# amp.net
KiCad netlist of a schematic drawn in EAGLE
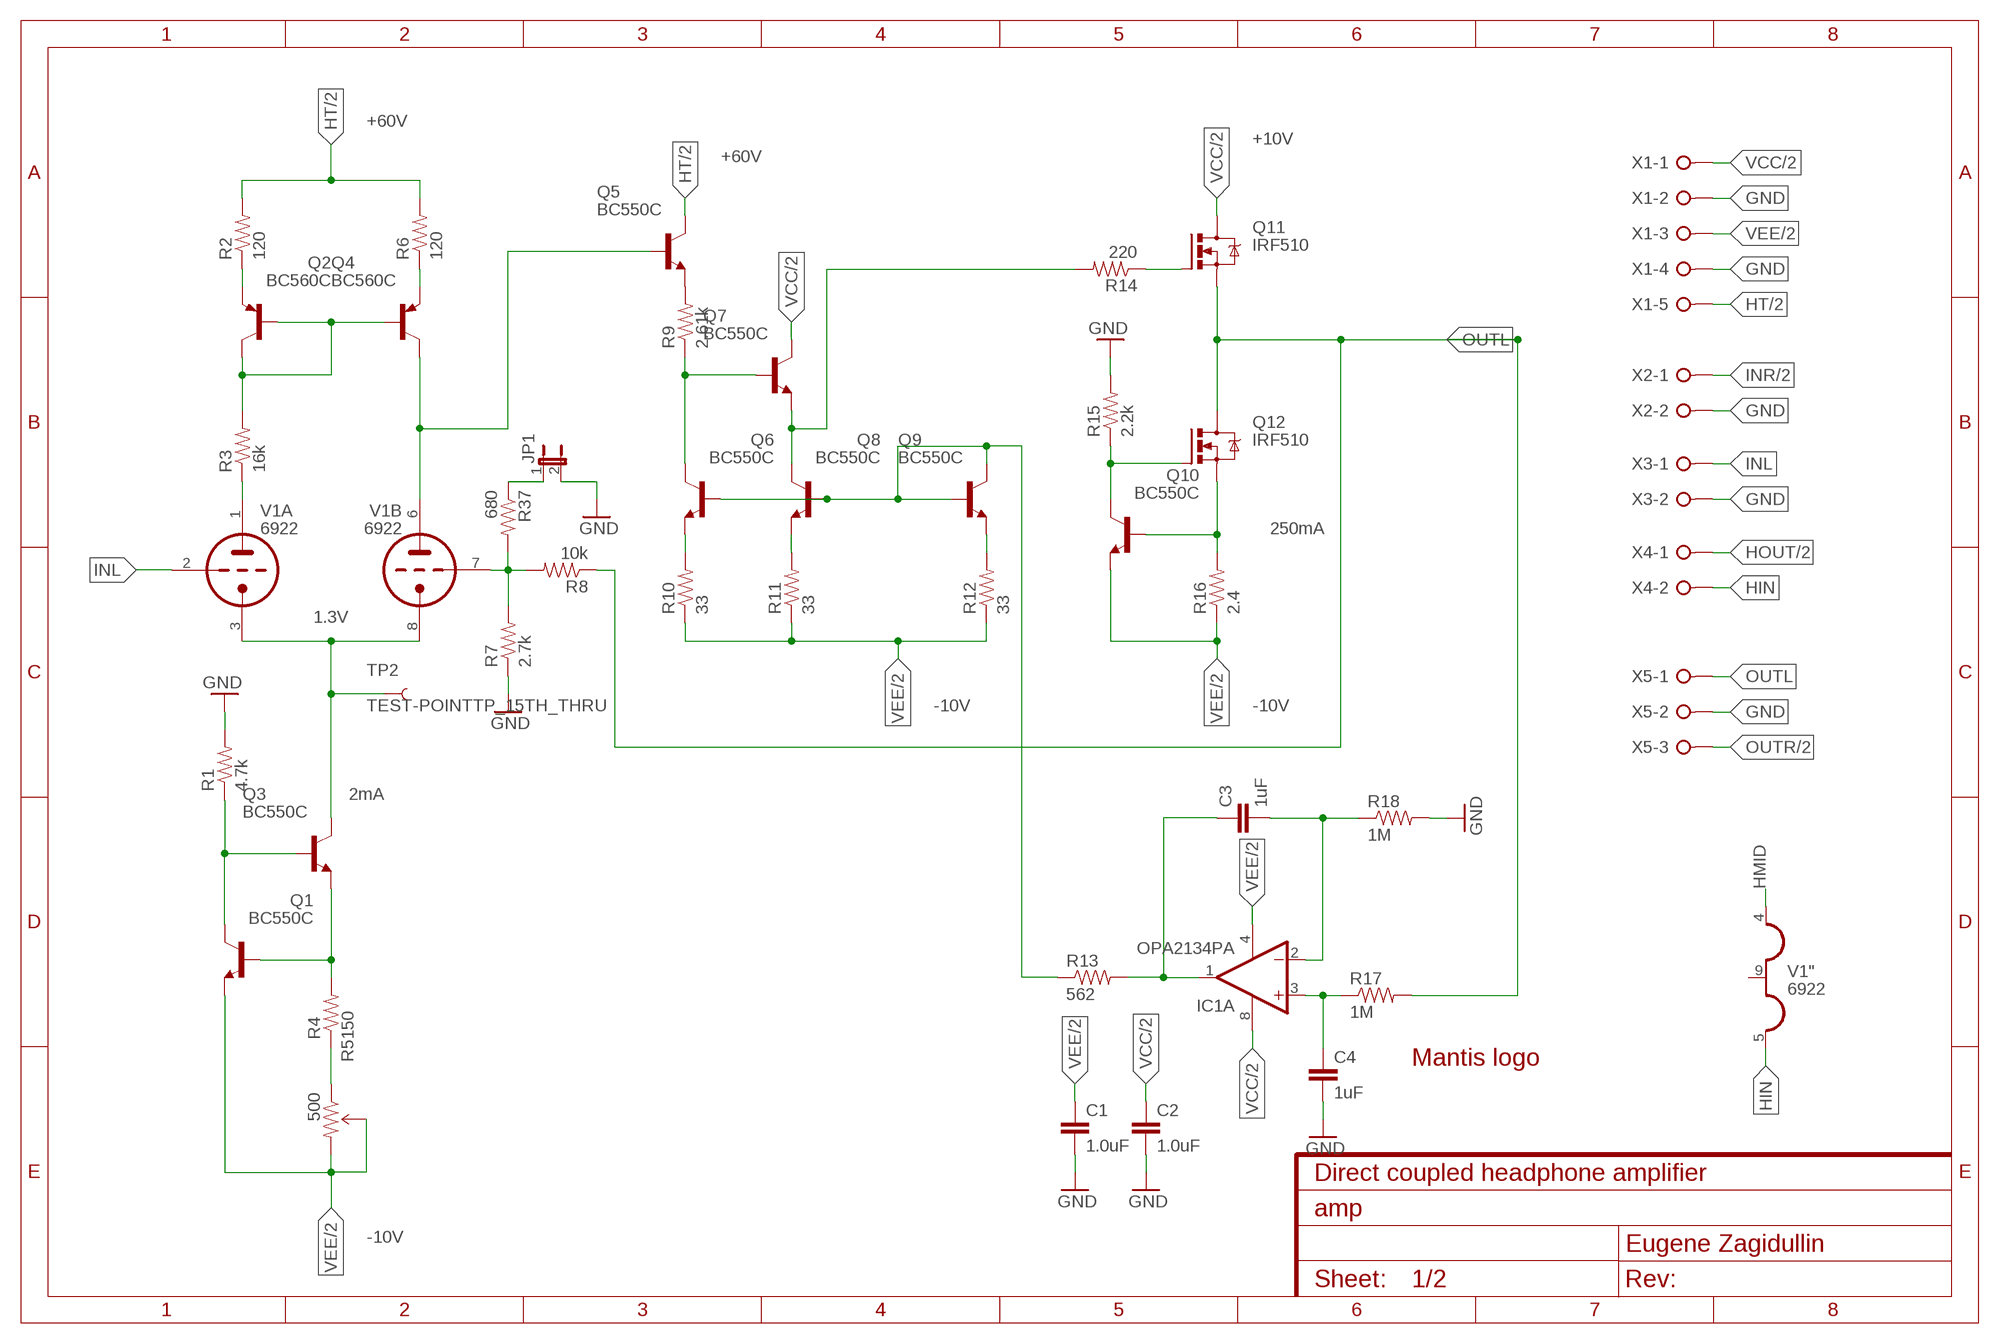
[diagram p0: schematic, sheet 1]
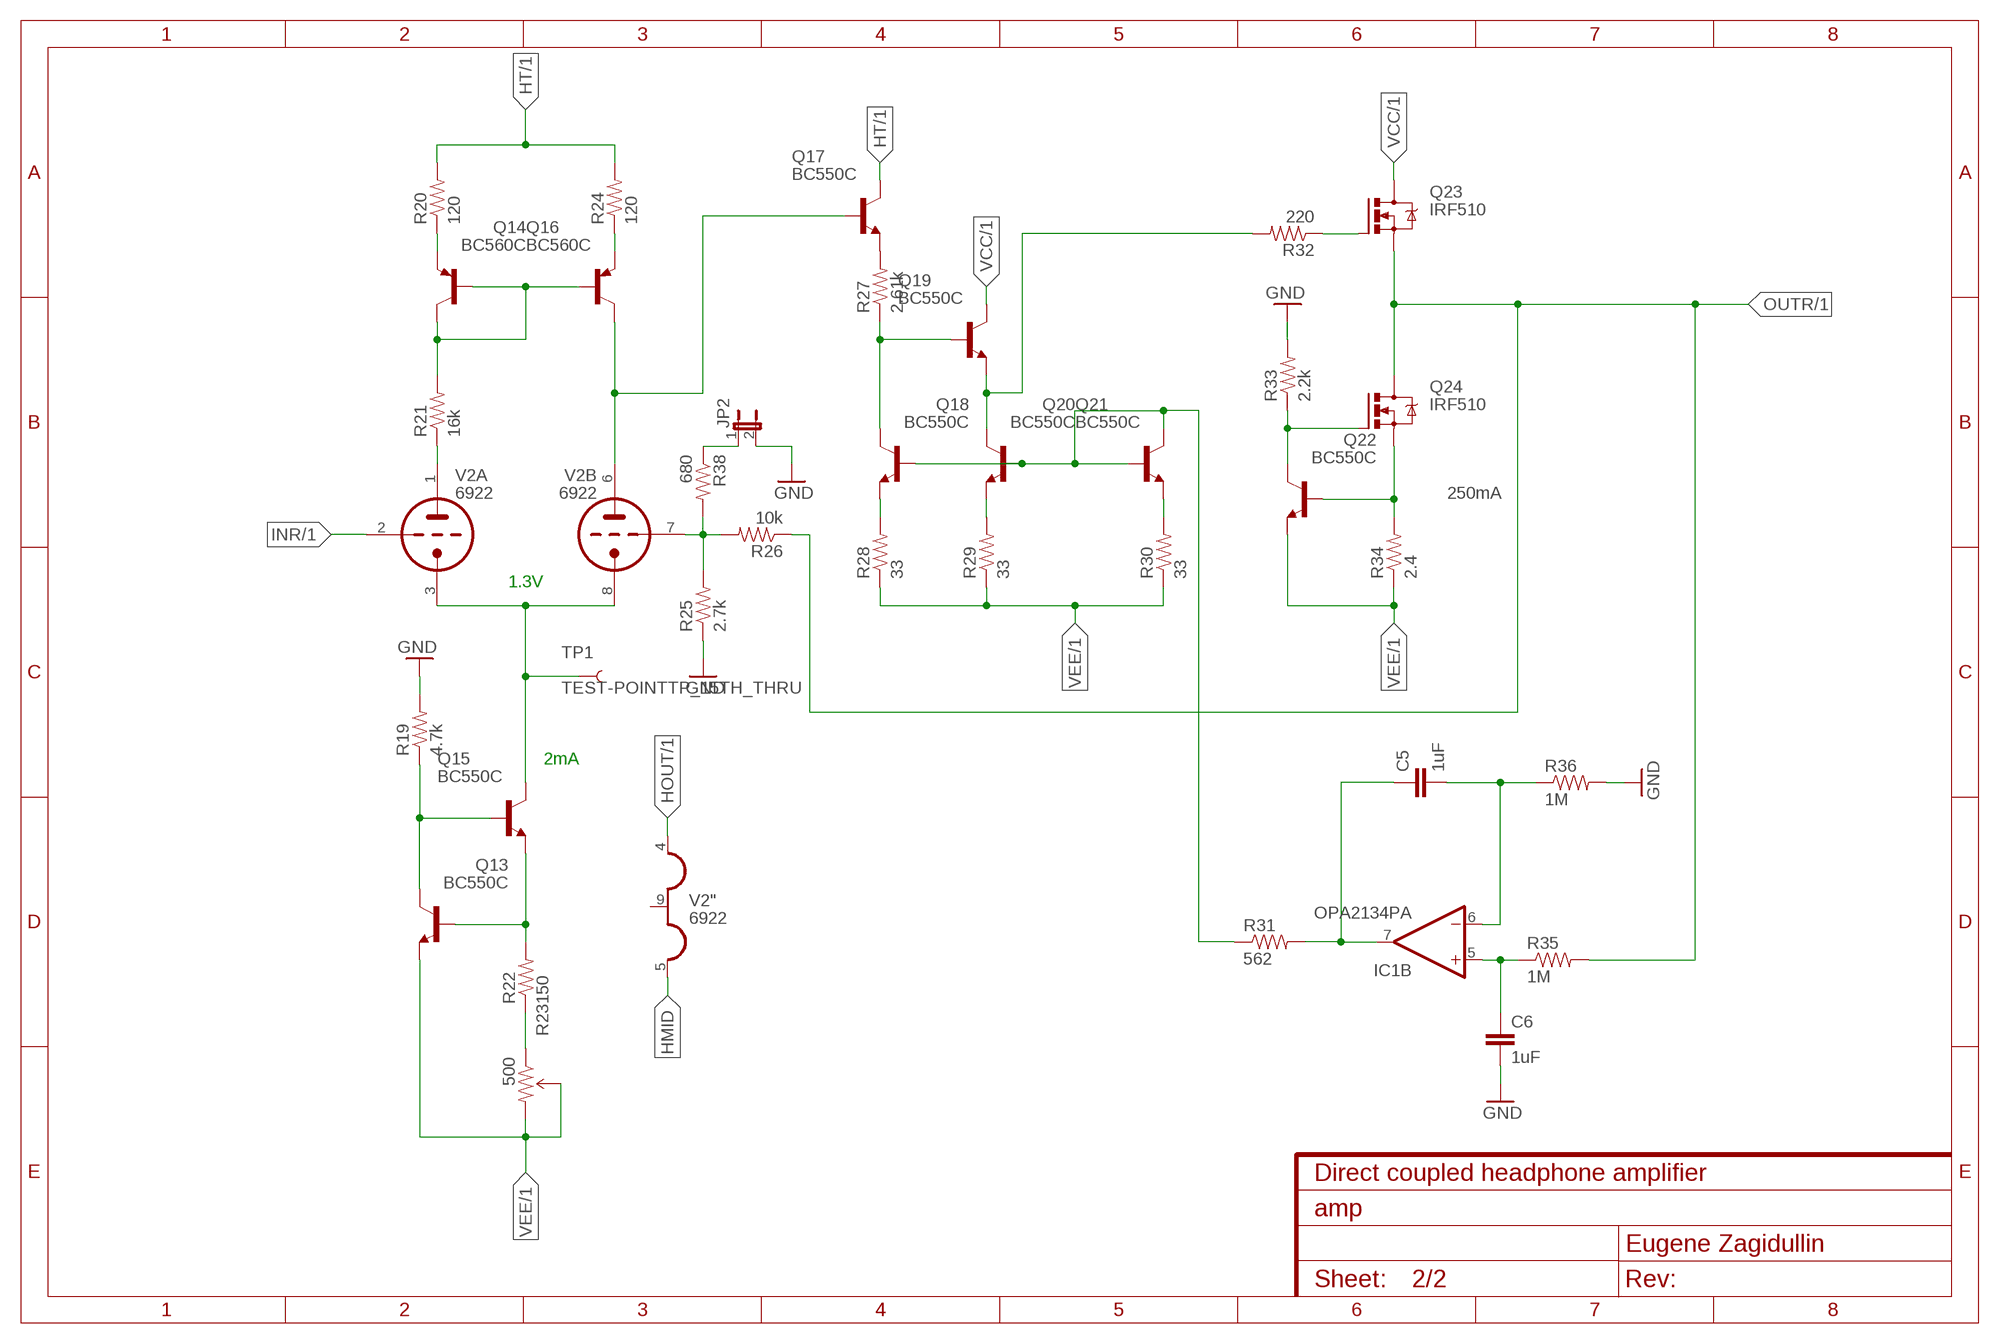
[diagram p1: schematic, sheet 2]

(export (version "E")
  (design (tool "Eeschema 10.0.6"))
  (components
    (comp (ref "C5")
      (value "1uF")
      (footprint "eagle-import:C5B5")
      (libsource (lib "eagle-import") (part "C5/5"))
    )
    (comp (ref "C6")
      (value "1uF")
      (footprint "eagle-import:C5B5")
      (libsource (lib "eagle-import") (part "C5/5"))
    )
    (comp (ref "IC1")
      (value "OPA2134PA")
      (footprint "eagle-import:DIL08")
      (libsource (lib "eagle-import") (part "OPA2PA134"))
    )
    (comp (ref "JP2")
      (value "JUMPER-2PTH")
      (footprint "eagle-import:1X02")
      (libsource (lib "eagle-import") (part "JUMPER-2PTH"))
    )
    (comp (ref "Q13")
      (value "BC550C")
      (footprint "eagle-import:TO92")
      (libsource (lib "eagle-import") (part "BC547"))
    )
    (comp (ref "Q14")
      (value "BC560C")
      (footprint "eagle-import:TO92-BENT")
      (libsource (lib "eagle-import") (part "BC556"))
    )
    (comp (ref "Q15")
      (value "BC550C")
      (footprint "eagle-import:TO92")
      (libsource (lib "eagle-import") (part "BC547"))
    )
    (comp (ref "Q16")
      (value "BC560C")
      (footprint "eagle-import:TO92-BENT")
      (libsource (lib "eagle-import") (part "BC556"))
    )
    (comp (ref "Q17")
      (value "BC550C")
      (footprint "eagle-import:TO92")
      (libsource (lib "eagle-import") (part "BC547"))
    )
    (comp (ref "Q18")
      (value "BC550C")
      (footprint "eagle-import:TO92")
      (libsource (lib "eagle-import") (part "BC547"))
    )
    (comp (ref "Q19")
      (value "BC550C")
      (footprint "eagle-import:TO92")
      (libsource (lib "eagle-import") (part "BC547"))
    )
    (comp (ref "Q20")
      (value "BC550C")
      (footprint "eagle-import:TO92")
      (libsource (lib "eagle-import") (part "BC547"))
    )
    (comp (ref "Q21")
      (value "BC550C")
      (footprint "eagle-import:TO92")
      (libsource (lib "eagle-import") (part "BC547"))
    )
    (comp (ref "Q22")
      (value "BC550C")
      (footprint "eagle-import:TO92")
      (libsource (lib "eagle-import") (part "BC547"))
    )
    (comp (ref "Q23")
      (value "IRF510")
      (footprint "eagle-import:TO220BV")
      (libsource (lib "eagle-import") (part "IRF540"))
    )
    (comp (ref "Q24")
      (value "IRF510")
      (footprint "eagle-import:TO220BV")
      (libsource (lib "eagle-import") (part "IRF540"))
    )
    (comp (ref "R19")
      (value "4.7k")
      (footprint "eagle-import:AXIAL-0.4")
      (libsource (lib "eagle-import") (part "RESISTORPTH-1/4W"))
    )
    (comp (ref "R20")
      (value "120")
      (footprint "eagle-import:AXIAL-0.4")
      (libsource (lib "eagle-import") (part "RESISTORPTH-1/4W"))
    )
    (comp (ref "R21")
      (value "16k")
      (footprint "eagle-import:AXIAL-0.4")
      (libsource (lib "eagle-import") (part "RESISTORPTH-1/4W"))
    )
    (comp (ref "R22")
      (value "150")
      (footprint "eagle-import:AXIAL-0.4")
      (libsource (lib "eagle-import") (part "RESISTORPTH-1/4W"))
    )
    (comp (ref "R23")
      (value "500")
      (footprint "eagle-import:3362U-2")
      (libsource (lib "eagle-import") (part "TRIMPOT3362U-2"))
    )
    (comp (ref "R24")
      (value "120")
      (footprint "eagle-import:AXIAL-0.4")
      (libsource (lib "eagle-import") (part "RESISTORPTH-1/4W"))
    )
    (comp (ref "R25")
      (value "2.7k")
      (footprint "eagle-import:AXIAL-0.4")
      (libsource (lib "eagle-import") (part "RESISTORPTH-1/4W"))
    )
    (comp (ref "R26")
      (value "10k")
      (footprint "eagle-import:AXIAL-0.4")
      (libsource (lib "eagle-import") (part "RESISTORPTH-1/4W"))
    )
    (comp (ref "R27")
      (value "2.61k")
      (footprint "eagle-import:AXIAL-0.4")
      (libsource (lib "eagle-import") (part "RESISTORPTH-1/4W"))
    )
    (comp (ref "R28")
      (value "33")
      (footprint "eagle-import:AXIAL-0.4")
      (libsource (lib "eagle-import") (part "RESISTORPTH-1/4W"))
    )
    (comp (ref "R29")
      (value "33")
      (footprint "eagle-import:AXIAL-0.4")
      (libsource (lib "eagle-import") (part "RESISTORPTH-1/4W"))
    )
    (comp (ref "R30")
      (value "33")
      (footprint "eagle-import:AXIAL-0.4")
      (libsource (lib "eagle-import") (part "RESISTORPTH-1/4W"))
    )
    (comp (ref "R31")
      (value "562")
      (footprint "eagle-import:AXIAL-0.4")
      (libsource (lib "eagle-import") (part "RESISTORPTH-1/4W"))
    )
    (comp (ref "R32")
      (value "220")
      (footprint "eagle-import:AXIAL-0.4")
      (libsource (lib "eagle-import") (part "RESISTORPTH-1/4W"))
    )
    (comp (ref "R33")
      (value "2.2k")
      (footprint "eagle-import:AXIAL-0.4")
      (libsource (lib "eagle-import") (part "RESISTORPTH-1/4W"))
    )
    (comp (ref "R34")
      (value "2.4")
      (footprint "eagle-import:AXIAL-0.5")
      (libsource (lib "eagle-import") (part "RESISTORPTH-1/2W"))
    )
    (comp (ref "R35")
      (value "1M")
      (footprint "eagle-import:AXIAL-0.4")
      (libsource (lib "eagle-import") (part "RESISTORPTH-1/4W"))
    )
    (comp (ref "R36")
      (value "1M")
      (footprint "eagle-import:AXIAL-0.4")
      (libsource (lib "eagle-import") (part "RESISTORPTH-1/4W"))
    )
    (comp (ref "R38")
      (value "680")
      (footprint "eagle-import:AXIAL-0.4")
      (libsource (lib "eagle-import") (part "RESISTORPTH-1/4W"))
    )
    (comp (ref "TP1")
      (value "TEST-POINTTP_15TH_THRU")
      (footprint "eagle-import:TP_15TH")
      (libsource (lib "eagle-import") (part "TEST-POINTTP_15TH_THRU"))
    )
    (comp (ref "V2")
      (value "6922")
      (footprint "eagle-import:NOVAL")
      (libsource (lib "eagle-import") (part "6922-P"))
    )
    (comp (ref "C1")
      (value "1.0uF")
      (footprint "eagle-import:0805-CAP")
      (libsource (lib "eagle-import") (part "1.0UF-25V-+80/-20(0805){dblquote}"))
    )
    (comp (ref "C2")
      (value "1.0uF")
      (footprint "eagle-import:0805-CAP")
      (libsource (lib "eagle-import") (part "1.0UF-25V-+80/-20(0805){dblquote}"))
    )
    (comp (ref "C3")
      (value "1uF")
      (footprint "eagle-import:C5B5")
      (libsource (lib "eagle-import") (part "C5/5"))
    )
    (comp (ref "C4")
      (value "1uF")
      (footprint "eagle-import:C5B5")
      (libsource (lib "eagle-import") (part "C5/5"))
    )
    (comp (ref "JP1")
      (value "JUMPER-2PTH")
      (footprint "eagle-import:1X02")
      (libsource (lib "eagle-import") (part "JUMPER-2PTH"))
    )
    (comp (ref "LOGO1")
      (value "LOGO-MANTIS")
      (footprint "eagle-import:LOGO-MANTIS")
      (libsource (lib "eagle-import") (part "LOGO-MANTIS"))
    )
    (comp (ref "Q1")
      (value "BC550C")
      (footprint "eagle-import:TO92")
      (libsource (lib "eagle-import") (part "BC547"))
    )
    (comp (ref "Q2")
      (value "BC560C")
      (footprint "eagle-import:TO92-BENT")
      (libsource (lib "eagle-import") (part "BC556"))
    )
    (comp (ref "Q3")
      (value "BC550C")
      (footprint "eagle-import:TO92")
      (libsource (lib "eagle-import") (part "BC547"))
    )
    (comp (ref "Q4")
      (value "BC560C")
      (footprint "eagle-import:TO92-BENT")
      (libsource (lib "eagle-import") (part "BC556"))
    )
    (comp (ref "Q5")
      (value "BC550C")
      (footprint "eagle-import:TO92")
      (libsource (lib "eagle-import") (part "BC547"))
    )
    (comp (ref "Q6")
      (value "BC550C")
      (footprint "eagle-import:TO92")
      (libsource (lib "eagle-import") (part "BC547"))
    )
    (comp (ref "Q7")
      (value "BC550C")
      (footprint "eagle-import:TO92")
      (libsource (lib "eagle-import") (part "BC547"))
    )
    (comp (ref "Q8")
      (value "BC550C")
      (footprint "eagle-import:TO92")
      (libsource (lib "eagle-import") (part "BC547"))
    )
    (comp (ref "Q9")
      (value "BC550C")
      (footprint "eagle-import:TO92")
      (libsource (lib "eagle-import") (part "BC547"))
    )
    (comp (ref "Q10")
      (value "BC550C")
      (footprint "eagle-import:TO92")
      (libsource (lib "eagle-import") (part "BC547"))
    )
    (comp (ref "Q11")
      (value "IRF510")
      (footprint "eagle-import:TO220BV")
      (libsource (lib "eagle-import") (part "IRF540"))
    )
    (comp (ref "Q12")
      (value "IRF510")
      (footprint "eagle-import:TO220BV")
      (libsource (lib "eagle-import") (part "IRF540"))
    )
    (comp (ref "R1")
      (value "4.7k")
      (footprint "eagle-import:AXIAL-0.4")
      (libsource (lib "eagle-import") (part "RESISTORPTH-1/4W"))
    )
    (comp (ref "R2")
      (value "120")
      (footprint "eagle-import:AXIAL-0.4")
      (libsource (lib "eagle-import") (part "RESISTORPTH-1/4W"))
    )
    (comp (ref "R3")
      (value "16k")
      (footprint "eagle-import:AXIAL-0.4")
      (libsource (lib "eagle-import") (part "RESISTORPTH-1/4W"))
    )
    (comp (ref "R4")
      (value "150")
      (footprint "eagle-import:AXIAL-0.4")
      (libsource (lib "eagle-import") (part "RESISTORPTH-1/4W"))
    )
    (comp (ref "R5")
      (value "500")
      (footprint "eagle-import:3362U-2")
      (libsource (lib "eagle-import") (part "TRIMPOT3362U-2"))
    )
    (comp (ref "R6")
      (value "120")
      (footprint "eagle-import:AXIAL-0.4")
      (libsource (lib "eagle-import") (part "RESISTORPTH-1/4W"))
    )
    (comp (ref "R7")
      (value "2.7k")
      (footprint "eagle-import:AXIAL-0.4")
      (libsource (lib "eagle-import") (part "RESISTORPTH-1/4W"))
    )
    (comp (ref "R8")
      (value "10k")
      (footprint "eagle-import:AXIAL-0.4")
      (libsource (lib "eagle-import") (part "RESISTORPTH-1/4W"))
    )
    (comp (ref "R9")
      (value "2.61k")
      (footprint "eagle-import:AXIAL-0.4")
      (libsource (lib "eagle-import") (part "RESISTORPTH-1/4W"))
    )
    (comp (ref "R10")
      (value "33")
      (footprint "eagle-import:AXIAL-0.4")
      (libsource (lib "eagle-import") (part "RESISTORPTH-1/4W"))
    )
    (comp (ref "R11")
      (value "33")
      (footprint "eagle-import:AXIAL-0.4")
      (libsource (lib "eagle-import") (part "RESISTORPTH-1/4W"))
    )
    (comp (ref "R12")
      (value "33")
      (footprint "eagle-import:AXIAL-0.4")
      (libsource (lib "eagle-import") (part "RESISTORPTH-1/4W"))
    )
    (comp (ref "R13")
      (value "562")
      (footprint "eagle-import:AXIAL-0.4")
      (libsource (lib "eagle-import") (part "RESISTORPTH-1/4W"))
    )
    (comp (ref "R14")
      (value "220")
      (footprint "eagle-import:AXIAL-0.4")
      (libsource (lib "eagle-import") (part "RESISTORPTH-1/4W"))
    )
    (comp (ref "R15")
      (value "2.2k")
      (footprint "eagle-import:AXIAL-0.4")
      (libsource (lib "eagle-import") (part "RESISTORPTH-1/4W"))
    )
    (comp (ref "R16")
      (value "2.4")
      (footprint "eagle-import:AXIAL-0.5")
      (libsource (lib "eagle-import") (part "RESISTORPTH-1/2W"))
    )
    (comp (ref "R17")
      (value "1M")
      (footprint "eagle-import:AXIAL-0.4")
      (libsource (lib "eagle-import") (part "RESISTORPTH-1/4W"))
    )
    (comp (ref "R18")
      (value "1M")
      (footprint "eagle-import:AXIAL-0.4")
      (libsource (lib "eagle-import") (part "RESISTORPTH-1/4W"))
    )
    (comp (ref "R37")
      (value "680")
      (footprint "eagle-import:AXIAL-0.4")
      (libsource (lib "eagle-import") (part "RESISTORPTH-1/4W"))
    )
    (comp (ref "TP2")
      (value "TEST-POINTTP_15TH_THRU")
      (footprint "eagle-import:TP_15TH")
      (libsource (lib "eagle-import") (part "TEST-POINTTP_15TH_THRU"))
    )
    (comp (ref "V1")
      (value "6922")
      (footprint "eagle-import:NOVAL")
      (libsource (lib "eagle-import") (part "6922-P"))
    )
    (comp (ref "X1")
      (value "W237-05P")
      (footprint "eagle-import:W237-5P")
      (libsource (lib "eagle-import") (part "W237-05P"))
    )
    (comp (ref "X2")
      (value "W237-02P")
      (footprint "eagle-import:W237-132")
      (libsource (lib "eagle-import") (part "W237-02P"))
    )
    (comp (ref "X3")
      (value "W237-02P")
      (footprint "eagle-import:W237-132")
      (libsource (lib "eagle-import") (part "W237-02P"))
    )
    (comp (ref "X4")
      (value "W237-02P")
      (footprint "eagle-import:W237-132")
      (libsource (lib "eagle-import") (part "W237-02P"))
    )
    (comp (ref "X5")
      (value "W237-3E")
      (footprint "eagle-import:W237-3E")
      (libsource (lib "eagle-import") (part "W237-3E"))
    )
  )
  (nets
    (net (code "1") (name "GND") (class "Default")
      (node (ref "C1") (pin "2") (pinfunction "2_2") (pintype "passive"))
      (node (ref "C2") (pin "2") (pinfunction "2_2") (pintype "passive"))
      (node (ref "C4") (pin "2") (pinfunction "2_2") (pintype "passive"))
      (node (ref "C6") (pin "2") (pinfunction "2_2") (pintype "passive"))
      (node (ref "JP1") (pin "2") (pinfunction "2_2") (pintype "passive"))
      (node (ref "JP2") (pin "2") (pinfunction "2_2") (pintype "passive"))
      (node (ref "R1") (pin "P$2") (pinfunction "2_P$2") (pintype "passive"))
      (node (ref "R15") (pin "P$2") (pinfunction "2_P$2") (pintype "passive"))
      (node (ref "R18") (pin "P$2") (pinfunction "2_P$2") (pintype "passive"))
      (node (ref "R19") (pin "P$2") (pinfunction "2_P$2") (pintype "passive"))
      (node (ref "R25") (pin "P$1") (pinfunction "1_P$1") (pintype "passive"))
      (node (ref "R33") (pin "P$2") (pinfunction "2_P$2") (pintype "passive"))
      (node (ref "R36") (pin "P$2") (pinfunction "2_P$2") (pintype "passive"))
      (node (ref "R7") (pin "P$1") (pinfunction "1_P$1") (pintype "passive"))
      (node (ref "X1") (pin "2") (pinfunction "KL_2") (pintype "passive"))
      (node (ref "X1") (pin "4") (pinfunction "KL_4") (pintype "passive"))
      (node (ref "X2") (pin "2") (pinfunction "KL_2") (pintype "passive"))
      (node (ref "X3") (pin "2") (pinfunction "KL_2") (pintype "passive"))
      (node (ref "X5") (pin "2") (pinfunction "KL_2") (pintype "passive"))
    )
    (net (code "2") (name "HIN") (class "Default")
      (node (ref "V1") (pin "5") (pinfunction "H3_5") (pintype "passive"))
      (node (ref "X4") (pin "2") (pinfunction "KL_2") (pintype "passive"))
    )
    (net (code "3") (name "HMID") (class "Default")
      (node (ref "V1") (pin "4") (pinfunction "H1_4") (pintype "passive"))
      (node (ref "V2") (pin "5") (pinfunction "H3_5") (pintype "passive"))
    )
    (net (code "4") (name "HOUT") (class "Default")
      (node (ref "V2") (pin "4") (pinfunction "H1_4") (pintype "passive"))
      (node (ref "X4") (pin "1") (pinfunction "KL_1") (pintype "passive"))
    )
    (net (code "5") (name "HT") (class "Default")
      (node (ref "Q17") (pin "3") (pinfunction "C_3") (pintype "passive"))
      (node (ref "Q5") (pin "3") (pinfunction "C_3") (pintype "passive"))
      (node (ref "R2") (pin "P$2") (pinfunction "2_P$2") (pintype "passive"))
      (node (ref "R20") (pin "P$2") (pinfunction "2_P$2") (pintype "passive"))
      (node (ref "R24") (pin "P$2") (pinfunction "2_P$2") (pintype "passive"))
      (node (ref "R6") (pin "P$2") (pinfunction "2_P$2") (pintype "passive"))
      (node (ref "X1") (pin "5") (pinfunction "KL_5") (pintype "passive"))
    )
    (net (code "6") (name "INL") (class "Default")
      (node (ref "V1") (pin "2") (pinfunction "TG_2") (pintype "passive"))
      (node (ref "X3") (pin "1") (pinfunction "KL_1") (pintype "passive"))
    )
    (net (code "7") (name "INR") (class "Default")
      (node (ref "V2") (pin "2") (pinfunction "TG_2") (pintype "passive"))
      (node (ref "X2") (pin "1") (pinfunction "KL_1") (pintype "passive"))
    )
    (net (code "8") (name "Net-(IC1A-+IN)") (class "Default")
      (node (ref "C4") (pin "1") (pinfunction "1_1") (pintype "passive"))
      (node (ref "IC1") (pin "3") (pinfunction "+IN_3") (pintype "input"))
      (node (ref "R17") (pin "P$1") (pinfunction "1_P$1") (pintype "passive"))
    )
    (net (code "9") (name "Net-(IC1A--IN)") (class "Default")
      (node (ref "C3") (pin "2") (pinfunction "2_2") (pintype "passive"))
      (node (ref "IC1") (pin "2") (pinfunction "-IN_2") (pintype "input"))
      (node (ref "R18") (pin "P$1") (pinfunction "1_P$1") (pintype "passive"))
    )
    (net (code "10") (name "Net-(IC1A-OUT)") (class "Default")
      (node (ref "C3") (pin "1") (pinfunction "1_1") (pintype "passive"))
      (node (ref "IC1") (pin "1") (pinfunction "OUT_1") (pintype "output"))
      (node (ref "R13") (pin "P$2") (pinfunction "2_P$2") (pintype "passive"))
    )
    (net (code "11") (name "Net-(IC1B-+IN)") (class "Default")
      (node (ref "C6") (pin "1") (pinfunction "1_1") (pintype "passive"))
      (node (ref "IC1") (pin "5") (pinfunction "+IN_5") (pintype "input"))
      (node (ref "R35") (pin "P$1") (pinfunction "1_P$1") (pintype "passive"))
    )
    (net (code "12") (name "Net-(IC1B--IN)") (class "Default")
      (node (ref "C5") (pin "2") (pinfunction "2_2") (pintype "passive"))
      (node (ref "IC1") (pin "6") (pinfunction "-IN_6") (pintype "input"))
      (node (ref "R36") (pin "P$1") (pinfunction "1_P$1") (pintype "passive"))
    )
    (net (code "13") (name "Net-(IC1B-OUT)") (class "Default")
      (node (ref "C5") (pin "1") (pinfunction "1_1") (pintype "passive"))
      (node (ref "IC1") (pin "7") (pinfunction "OUT_7") (pintype "output"))
      (node (ref "R31") (pin "P$2") (pinfunction "2_P$2") (pintype "passive"))
    )
    (net (code "14") (name "Net-(Q1-B)") (class "Default")
      (node (ref "Q1") (pin "2") (pinfunction "B_2") (pintype "passive"))
      (node (ref "Q3") (pin "1") (pinfunction "E_1") (pintype "passive"))
      (node (ref "R4") (pin "P$2") (pinfunction "2_P$2") (pintype "passive"))
    )
    (net (code "15") (name "Net-(Q1-C)") (class "Default")
      (node (ref "Q1") (pin "3") (pinfunction "C_3") (pintype "passive"))
      (node (ref "Q3") (pin "2") (pinfunction "B_2") (pintype "passive"))
      (node (ref "R1") (pin "P$1") (pinfunction "1_P$1") (pintype "passive"))
    )
    (net (code "16") (name "Net-(Q2-B)") (class "Default")
      (node (ref "Q2") (pin "1") (pinfunction "C_1") (pintype "passive"))
      (node (ref "Q2") (pin "2") (pinfunction "B_2") (pintype "passive"))
      (node (ref "Q4") (pin "2") (pinfunction "B_2") (pintype "passive"))
      (node (ref "R3") (pin "P$2") (pinfunction "2_P$2") (pintype "passive"))
    )
    (net (code "17") (name "Net-(Q2-E)") (class "Default")
      (node (ref "Q2") (pin "3") (pinfunction "E_3") (pintype "passive"))
      (node (ref "R2") (pin "P$1") (pinfunction "1_P$1") (pintype "passive"))
    )
    (net (code "18") (name "Net-(Q3-C)") (class "Default")
      (node (ref "Q3") (pin "3") (pinfunction "C_3") (pintype "passive"))
      (node (ref "TP2") (pin "P$1") (pinfunction "1_P$1") (pintype "bidirectional"))
      (node (ref "V1") (pin "3") (pinfunction "TK_3") (pintype "passive"))
      (node (ref "V1") (pin "8") (pinfunction "TK_8") (pintype "passive"))
    )
    (net (code "19") (name "Net-(Q4-C)") (class "Default")
      (node (ref "Q4") (pin "1") (pinfunction "C_1") (pintype "passive"))
      (node (ref "Q5") (pin "2") (pinfunction "B_2") (pintype "passive"))
      (node (ref "V1") (pin "6") (pinfunction "TA_6") (pintype "passive"))
    )
    (net (code "20") (name "Net-(Q4-E)") (class "Default")
      (node (ref "Q4") (pin "3") (pinfunction "E_3") (pintype "passive"))
      (node (ref "R6") (pin "P$1") (pinfunction "1_P$1") (pintype "passive"))
    )
    (net (code "21") (name "Net-(Q5-E)") (class "Default")
      (node (ref "Q5") (pin "1") (pinfunction "E_1") (pintype "passive"))
      (node (ref "R9") (pin "P$2") (pinfunction "2_P$2") (pintype "passive"))
    )
    (net (code "22") (name "Net-(Q6-B)") (class "Default")
      (node (ref "Q6") (pin "2") (pinfunction "B_2") (pintype "passive"))
      (node (ref "Q8") (pin "2") (pinfunction "B_2") (pintype "passive"))
      (node (ref "Q9") (pin "2") (pinfunction "B_2") (pintype "passive"))
      (node (ref "Q9") (pin "3") (pinfunction "C_3") (pintype "passive"))
      (node (ref "R13") (pin "P$1") (pinfunction "1_P$1") (pintype "passive"))
    )
    (net (code "23") (name "Net-(Q6-C)") (class "Default")
      (node (ref "Q6") (pin "3") (pinfunction "C_3") (pintype "passive"))
      (node (ref "Q7") (pin "2") (pinfunction "B_2") (pintype "passive"))
      (node (ref "R9") (pin "P$1") (pinfunction "1_P$1") (pintype "passive"))
    )
    (net (code "24") (name "Net-(Q6-E)") (class "Default")
      (node (ref "Q6") (pin "1") (pinfunction "E_1") (pintype "passive"))
      (node (ref "R10") (pin "P$2") (pinfunction "2_P$2") (pintype "passive"))
    )
    (net (code "25") (name "Net-(Q7-E)") (class "Default")
      (node (ref "Q7") (pin "1") (pinfunction "E_1") (pintype "passive"))
      (node (ref "Q8") (pin "3") (pinfunction "C_3") (pintype "passive"))
      (node (ref "R14") (pin "P$2") (pinfunction "2_P$2") (pintype "passive"))
    )
    (net (code "26") (name "Net-(Q8-E)") (class "Default")
      (node (ref "Q8") (pin "1") (pinfunction "E_1") (pintype "passive"))
      (node (ref "R11") (pin "P$2") (pinfunction "2_P$2") (pintype "passive"))
    )
    (net (code "27") (name "Net-(Q9-E)") (class "Default")
      (node (ref "Q9") (pin "1") (pinfunction "E_1") (pintype "passive"))
      (node (ref "R12") (pin "P$2") (pinfunction "2_P$2") (pintype "passive"))
    )
    (net (code "28") (name "Net-(Q10-B)") (class "Default")
      (node (ref "Q10") (pin "2") (pinfunction "B_2") (pintype "passive"))
      (node (ref "Q12") (pin "S") (pinfunction "S_S") (pintype "passive"))
      (node (ref "R16") (pin "P$2") (pinfunction "2_P$2") (pintype "passive"))
    )
    (net (code "29") (name "Net-(Q10-C)") (class "Default")
      (node (ref "Q10") (pin "3") (pinfunction "C_3") (pintype "passive"))
      (node (ref "Q12") (pin "G") (pinfunction "G_G") (pintype "passive"))
      (node (ref "R15") (pin "P$1") (pinfunction "1_P$1") (pintype "passive"))
    )
    (net (code "30") (name "Net-(Q13-B)") (class "Default")
      (node (ref "Q13") (pin "2") (pinfunction "B_2") (pintype "passive"))
      (node (ref "Q15") (pin "1") (pinfunction "E_1") (pintype "passive"))
      (node (ref "R22") (pin "P$2") (pinfunction "2_P$2") (pintype "passive"))
    )
    (net (code "31") (name "Net-(Q13-C)") (class "Default")
      (node (ref "Q13") (pin "3") (pinfunction "C_3") (pintype "passive"))
      (node (ref "Q15") (pin "2") (pinfunction "B_2") (pintype "passive"))
      (node (ref "R19") (pin "P$1") (pinfunction "1_P$1") (pintype "passive"))
    )
    (net (code "32") (name "Net-(Q14-B)") (class "Default")
      (node (ref "Q14") (pin "1") (pinfunction "C_1") (pintype "passive"))
      (node (ref "Q14") (pin "2") (pinfunction "B_2") (pintype "passive"))
      (node (ref "Q16") (pin "2") (pinfunction "B_2") (pintype "passive"))
      (node (ref "R21") (pin "P$2") (pinfunction "2_P$2") (pintype "passive"))
    )
    (net (code "33") (name "Net-(Q14-E)") (class "Default")
      (node (ref "Q14") (pin "3") (pinfunction "E_3") (pintype "passive"))
      (node (ref "R20") (pin "P$1") (pinfunction "1_P$1") (pintype "passive"))
    )
    (net (code "34") (name "Net-(Q15-C)") (class "Default")
      (node (ref "Q15") (pin "3") (pinfunction "C_3") (pintype "passive"))
      (node (ref "TP1") (pin "P$1") (pinfunction "1_P$1") (pintype "bidirectional"))
      (node (ref "V2") (pin "3") (pinfunction "TK_3") (pintype "passive"))
      (node (ref "V2") (pin "8") (pinfunction "TK_8") (pintype "passive"))
    )
    (net (code "35") (name "Net-(Q16-C)") (class "Default")
      (node (ref "Q16") (pin "1") (pinfunction "C_1") (pintype "passive"))
      (node (ref "Q17") (pin "2") (pinfunction "B_2") (pintype "passive"))
      (node (ref "V2") (pin "6") (pinfunction "TA_6") (pintype "passive"))
    )
    (net (code "36") (name "Net-(Q16-E)") (class "Default")
      (node (ref "Q16") (pin "3") (pinfunction "E_3") (pintype "passive"))
      (node (ref "R24") (pin "P$1") (pinfunction "1_P$1") (pintype "passive"))
    )
    (net (code "37") (name "Net-(Q17-E)") (class "Default")
      (node (ref "Q17") (pin "1") (pinfunction "E_1") (pintype "passive"))
      (node (ref "R27") (pin "P$2") (pinfunction "2_P$2") (pintype "passive"))
    )
    (net (code "38") (name "Net-(Q18-B)") (class "Default")
      (node (ref "Q18") (pin "2") (pinfunction "B_2") (pintype "passive"))
      (node (ref "Q20") (pin "2") (pinfunction "B_2") (pintype "passive"))
      (node (ref "Q21") (pin "2") (pinfunction "B_2") (pintype "passive"))
      (node (ref "Q21") (pin "3") (pinfunction "C_3") (pintype "passive"))
      (node (ref "R31") (pin "P$1") (pinfunction "1_P$1") (pintype "passive"))
    )
    (net (code "39") (name "Net-(Q18-C)") (class "Default")
      (node (ref "Q18") (pin "3") (pinfunction "C_3") (pintype "passive"))
      (node (ref "Q19") (pin "2") (pinfunction "B_2") (pintype "passive"))
      (node (ref "R27") (pin "P$1") (pinfunction "1_P$1") (pintype "passive"))
    )
    (net (code "40") (name "Net-(Q18-E)") (class "Default")
      (node (ref "Q18") (pin "1") (pinfunction "E_1") (pintype "passive"))
      (node (ref "R28") (pin "P$2") (pinfunction "2_P$2") (pintype "passive"))
    )
    (net (code "41") (name "Net-(Q19-E)") (class "Default")
      (node (ref "Q19") (pin "1") (pinfunction "E_1") (pintype "passive"))
      (node (ref "Q20") (pin "3") (pinfunction "C_3") (pintype "passive"))
      (node (ref "R32") (pin "P$2") (pinfunction "2_P$2") (pintype "passive"))
    )
    (net (code "42") (name "Net-(Q20-E)") (class "Default")
      (node (ref "Q20") (pin "1") (pinfunction "E_1") (pintype "passive"))
      (node (ref "R29") (pin "P$2") (pinfunction "2_P$2") (pintype "passive"))
    )
    (net (code "43") (name "Net-(Q21-E)") (class "Default")
      (node (ref "Q21") (pin "1") (pinfunction "E_1") (pintype "passive"))
      (node (ref "R30") (pin "P$2") (pinfunction "2_P$2") (pintype "passive"))
    )
    (net (code "44") (name "Net-(Q22-B)") (class "Default")
      (node (ref "Q22") (pin "2") (pinfunction "B_2") (pintype "passive"))
      (node (ref "Q24") (pin "S") (pinfunction "S_S") (pintype "passive"))
      (node (ref "R34") (pin "P$2") (pinfunction "2_P$2") (pintype "passive"))
    )
    (net (code "45") (name "Net-(Q22-C)") (class "Default")
      (node (ref "Q22") (pin "3") (pinfunction "C_3") (pintype "passive"))
      (node (ref "Q24") (pin "G") (pinfunction "G_G") (pintype "passive"))
      (node (ref "R33") (pin "P$1") (pinfunction "1_P$1") (pintype "passive"))
    )
    (net (code "46") (name "Net-(R3-1)") (class "Default")
      (node (ref "R3") (pin "P$1") (pinfunction "1_P$1") (pintype "passive"))
      (node (ref "V1") (pin "1") (pinfunction "TA_1") (pintype "passive"))
    )
    (net (code "47") (name "Net-(R4-1)") (class "Default")
      (node (ref "R4") (pin "P$1") (pinfunction "1_P$1") (pintype "passive"))
      (node (ref "R5") (pin "1") (pinfunction "CCW_1") (pintype "passive"))
    )
    (net (code "48") (name "Net-(R14-1)") (class "Default")
      (node (ref "Q11") (pin "G") (pinfunction "G_G") (pintype "passive"))
      (node (ref "R14") (pin "P$1") (pinfunction "1_P$1") (pintype "passive"))
    )
    (net (code "49") (name "Net-(R21-1)") (class "Default")
      (node (ref "R21") (pin "P$1") (pinfunction "1_P$1") (pintype "passive"))
      (node (ref "V2") (pin "1") (pinfunction "TA_1") (pintype "passive"))
    )
    (net (code "50") (name "Net-(R22-1)") (class "Default")
      (node (ref "R22") (pin "P$1") (pinfunction "1_P$1") (pintype "passive"))
      (node (ref "R23") (pin "1") (pinfunction "CCW_1") (pintype "passive"))
    )
    (net (code "51") (name "Net-(R25-2)") (class "Default")
      (node (ref "R25") (pin "P$2") (pinfunction "2_P$2") (pintype "passive"))
      (node (ref "R26") (pin "P$2") (pinfunction "2_P$2") (pintype "passive"))
      (node (ref "R38") (pin "P$2") (pinfunction "2_P$2") (pintype "passive"))
      (node (ref "V2") (pin "7") (pinfunction "TG_7") (pintype "passive"))
    )
    (net (code "52") (name "Net-(R32-1)") (class "Default")
      (node (ref "Q23") (pin "G") (pinfunction "G_G") (pintype "passive"))
      (node (ref "R32") (pin "P$1") (pinfunction "1_P$1") (pintype "passive"))
    )
    (net (code "53") (name "Net-(R37-1)") (class "Default")
      (node (ref "JP1") (pin "1") (pinfunction "1_1") (pintype "passive"))
      (node (ref "R37") (pin "P$1") (pinfunction "1_P$1") (pintype "passive"))
    )
    (net (code "54") (name "Net-(R37-2)") (class "Default")
      (node (ref "R37") (pin "P$2") (pinfunction "2_P$2") (pintype "passive"))
      (node (ref "R7") (pin "P$2") (pinfunction "2_P$2") (pintype "passive"))
      (node (ref "R8") (pin "P$2") (pinfunction "2_P$2") (pintype "passive"))
      (node (ref "V1") (pin "7") (pinfunction "TG_7") (pintype "passive"))
    )
    (net (code "55") (name "Net-(R38-1)") (class "Default")
      (node (ref "JP2") (pin "1") (pinfunction "1_1") (pintype "passive"))
      (node (ref "R38") (pin "P$1") (pinfunction "1_P$1") (pintype "passive"))
    )
    (net (code "56") (name "OUTL") (class "Default")
      (node (ref "Q11") (pin "S") (pinfunction "S_S") (pintype "passive"))
      (node (ref "Q12") (pin "D") (pinfunction "D_D") (pintype "passive"))
      (node (ref "R17") (pin "P$2") (pinfunction "2_P$2") (pintype "passive"))
      (node (ref "R8") (pin "P$1") (pinfunction "1_P$1") (pintype "passive"))
      (node (ref "X5") (pin "1") (pinfunction "KL_1") (pintype "passive"))
    )
    (net (code "57") (name "OUTR") (class "Default")
      (node (ref "Q23") (pin "S") (pinfunction "S_S") (pintype "passive"))
      (node (ref "Q24") (pin "D") (pinfunction "D_D") (pintype "passive"))
      (node (ref "R26") (pin "P$1") (pinfunction "1_P$1") (pintype "passive"))
      (node (ref "R35") (pin "P$2") (pinfunction "2_P$2") (pintype "passive"))
      (node (ref "X5") (pin "3") (pinfunction "KL_3") (pintype "passive"))
    )
    (net (code "58") (name "VCC") (class "Default")
      (node (ref "C2") (pin "1") (pinfunction "1_1") (pintype "passive"))
      (node (ref "IC1") (pin "8") (pinfunction "V+_8") (pintype "power_in"))
      (node (ref "Q11") (pin "D") (pinfunction "D_D") (pintype "passive"))
      (node (ref "Q19") (pin "3") (pinfunction "C_3") (pintype "passive"))
      (node (ref "Q23") (pin "D") (pinfunction "D_D") (pintype "passive"))
      (node (ref "Q7") (pin "3") (pinfunction "C_3") (pintype "passive"))
      (node (ref "X1") (pin "1") (pinfunction "KL_1") (pintype "passive"))
    )
    (net (code "59") (name "VEE") (class "Default")
      (node (ref "C1") (pin "1") (pinfunction "1_1") (pintype "passive"))
      (node (ref "IC1") (pin "4") (pinfunction "V-_4") (pintype "power_in"))
      (node (ref "Q1") (pin "1") (pinfunction "E_1") (pintype "passive"))
      (node (ref "Q10") (pin "1") (pinfunction "E_1") (pintype "passive"))
      (node (ref "Q13") (pin "1") (pinfunction "E_1") (pintype "passive"))
      (node (ref "Q22") (pin "1") (pinfunction "E_1") (pintype "passive"))
      (node (ref "R10") (pin "P$1") (pinfunction "1_P$1") (pintype "passive"))
      (node (ref "R11") (pin "P$1") (pinfunction "1_P$1") (pintype "passive"))
      (node (ref "R12") (pin "P$1") (pinfunction "1_P$1") (pintype "passive"))
      (node (ref "R16") (pin "P$1") (pinfunction "1_P$1") (pintype "passive"))
      (node (ref "R23") (pin "2") (pinfunction "WIPER_2") (pintype "passive"))
      (node (ref "R23") (pin "3") (pinfunction "CW_3") (pintype "passive"))
      (node (ref "R28") (pin "P$1") (pinfunction "1_P$1") (pintype "passive"))
      (node (ref "R29") (pin "P$1") (pinfunction "1_P$1") (pintype "passive"))
      (node (ref "R30") (pin "P$1") (pinfunction "1_P$1") (pintype "passive"))
      (node (ref "R34") (pin "P$1") (pinfunction "1_P$1") (pintype "passive"))
      (node (ref "R5") (pin "2") (pinfunction "WIPER_2") (pintype "passive"))
      (node (ref "R5") (pin "3") (pinfunction "CW_3") (pintype "passive"))
      (node (ref "X1") (pin "3") (pinfunction "KL_3") (pintype "passive"))
    )
    (net (code "60") (name "unconnected-(V1A-H2-Pad9)") (class "Default")
      (node (ref "V1") (pin "9") (pinfunction "H2_9") (pintype "passive"))
    )
    (net (code "61") (name "unconnected-(V2A-H2-Pad9)") (class "Default")
      (node (ref "V2") (pin "9") (pinfunction "H2_9") (pintype "passive"))
    )
  )
)
